# B134X.net
KiCad netlist of a schematic drawn in EAGLE
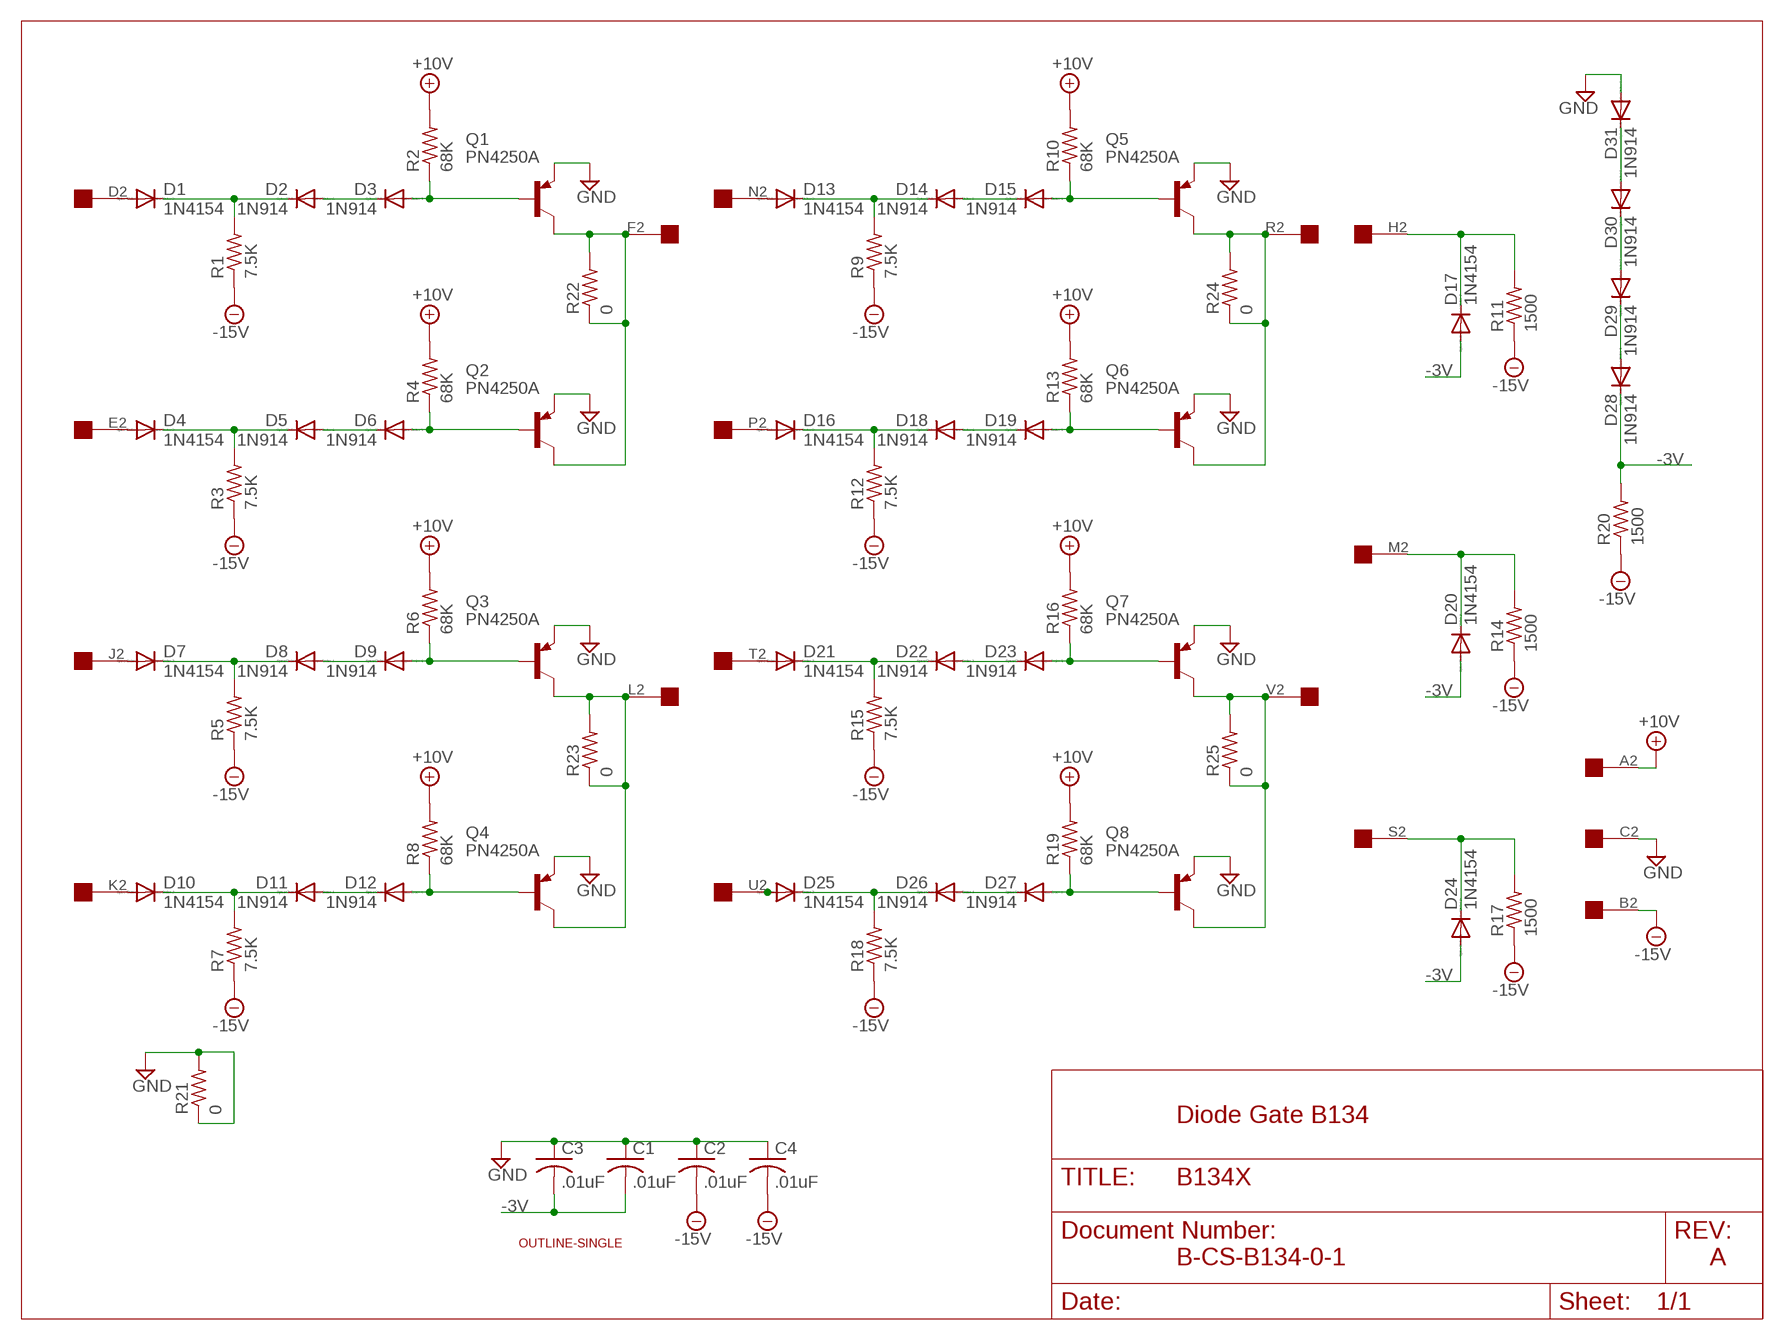
[diagram p0: schematic, sheet 1]

(export (version "E")
  (design (tool "Eeschema 10.0.6"))
  (components
    (comp (ref "C1")
      (value ".01uF")
      (footprint "eagle-import:C063-025X075")
      (libsource (lib "eagle-import") (part "C-US"))
    )
    (comp (ref "C2")
      (value ".01uF")
      (footprint "eagle-import:C063-025X075")
      (libsource (lib "eagle-import") (part "C-US"))
    )
    (comp (ref "C3")
      (value ".01uF")
      (footprint "eagle-import:C063-025X075")
      (libsource (lib "eagle-import") (part "C-US"))
    )
    (comp (ref "C4")
      (value ".01uF")
      (footprint "eagle-import:C063-025X075")
      (libsource (lib "eagle-import") (part "C-US"))
    )
    (comp (ref "D1")
      (value "1N4154")
      (footprint "eagle-import:DO35-10")
      (libsource (lib "eagle-import") (part "DIODE-DO35-10"))
    )
    (comp (ref "D2")
      (value "1N914")
      (footprint "eagle-import:DO35-10")
      (libsource (lib "eagle-import") (part "DIODE-DO35-10"))
    )
    (comp (ref "D3")
      (value "1N914")
      (footprint "eagle-import:DO35-10")
      (libsource (lib "eagle-import") (part "DIODE-DO35-10"))
    )
    (comp (ref "D4")
      (value "1N4154")
      (footprint "eagle-import:DO35-10")
      (libsource (lib "eagle-import") (part "DIODE-DO35-10"))
    )
    (comp (ref "D5")
      (value "1N914")
      (footprint "eagle-import:DO35-10")
      (libsource (lib "eagle-import") (part "DIODE-DO35-10"))
    )
    (comp (ref "D6")
      (value "1N914")
      (footprint "eagle-import:DO35-10")
      (libsource (lib "eagle-import") (part "DIODE-DO35-10"))
    )
    (comp (ref "D7")
      (value "1N4154")
      (footprint "eagle-import:DO35-10")
      (libsource (lib "eagle-import") (part "DIODE-DO35-10"))
    )
    (comp (ref "D8")
      (value "1N914")
      (footprint "eagle-import:DO35-10")
      (libsource (lib "eagle-import") (part "DIODE-DO35-10"))
    )
    (comp (ref "D9")
      (value "1N914")
      (footprint "eagle-import:DO35-10")
      (libsource (lib "eagle-import") (part "DIODE-DO35-10"))
    )
    (comp (ref "D10")
      (value "1N4154")
      (footprint "eagle-import:DO35-10")
      (libsource (lib "eagle-import") (part "DIODE-DO35-10"))
    )
    (comp (ref "D11")
      (value "1N914")
      (footprint "eagle-import:DO35-10")
      (libsource (lib "eagle-import") (part "DIODE-DO35-10"))
    )
    (comp (ref "D12")
      (value "1N914")
      (footprint "eagle-import:DO35-10")
      (libsource (lib "eagle-import") (part "DIODE-DO35-10"))
    )
    (comp (ref "D13")
      (value "1N4154")
      (footprint "eagle-import:DO35-10")
      (libsource (lib "eagle-import") (part "DIODE-DO35-10"))
    )
    (comp (ref "D14")
      (value "1N914")
      (footprint "eagle-import:DO35-10")
      (libsource (lib "eagle-import") (part "DIODE-DO35-10"))
    )
    (comp (ref "D15")
      (value "1N914")
      (footprint "eagle-import:DO35-10")
      (libsource (lib "eagle-import") (part "DIODE-DO35-10"))
    )
    (comp (ref "D16")
      (value "1N4154")
      (footprint "eagle-import:DO35-10")
      (libsource (lib "eagle-import") (part "DIODE-DO35-10"))
    )
    (comp (ref "D17")
      (value "1N4154")
      (footprint "eagle-import:DO35-10")
      (libsource (lib "eagle-import") (part "DIODE-DO35-10"))
    )
    (comp (ref "D18")
      (value "1N914")
      (footprint "eagle-import:DO35-10")
      (libsource (lib "eagle-import") (part "DIODE-DO35-10"))
    )
    (comp (ref "D19")
      (value "1N914")
      (footprint "eagle-import:DO35-10")
      (libsource (lib "eagle-import") (part "DIODE-DO35-10"))
    )
    (comp (ref "D20")
      (value "1N4154")
      (footprint "eagle-import:DO35-10")
      (libsource (lib "eagle-import") (part "DIODE-DO35-10"))
    )
    (comp (ref "D21")
      (value "1N4154")
      (footprint "eagle-import:DO35-10")
      (libsource (lib "eagle-import") (part "DIODE-DO35-10"))
    )
    (comp (ref "D22")
      (value "1N914")
      (footprint "eagle-import:DO35-10")
      (libsource (lib "eagle-import") (part "DIODE-DO35-10"))
    )
    (comp (ref "D23")
      (value "1N914")
      (footprint "eagle-import:DO35-10")
      (libsource (lib "eagle-import") (part "DIODE-DO35-10"))
    )
    (comp (ref "D24")
      (value "1N4154")
      (footprint "eagle-import:DO35-10")
      (libsource (lib "eagle-import") (part "DIODE-DO35-10"))
    )
    (comp (ref "D25")
      (value "1N4154")
      (footprint "eagle-import:DO35-10")
      (libsource (lib "eagle-import") (part "DIODE-DO35-10"))
    )
    (comp (ref "D26")
      (value "1N914")
      (footprint "eagle-import:DO35-10")
      (libsource (lib "eagle-import") (part "DIODE-DO35-10"))
    )
    (comp (ref "D27")
      (value "1N914")
      (footprint "eagle-import:DO35-10")
      (libsource (lib "eagle-import") (part "DIODE-DO35-10"))
    )
    (comp (ref "D28")
      (value "1N914")
      (footprint "eagle-import:DO35-10")
      (libsource (lib "eagle-import") (part "DIODE-DO35-10"))
    )
    (comp (ref "D29")
      (value "1N914")
      (footprint "eagle-import:DO35-10")
      (libsource (lib "eagle-import") (part "DIODE-DO35-10"))
    )
    (comp (ref "D30")
      (value "1N914")
      (footprint "eagle-import:DO35-10")
      (libsource (lib "eagle-import") (part "DIODE-DO35-10"))
    )
    (comp (ref "D31")
      (value "1N914")
      (footprint "eagle-import:DO35-10")
      (libsource (lib "eagle-import") (part "DIODE-DO35-10"))
    )
    (comp (ref "Q1")
      (value "PN4250A")
      (footprint "eagle-import:TO5")
      (libsource (lib "eagle-import") (part "-PNP-TO5"))
    )
    (comp (ref "Q2")
      (value "PN4250A")
      (footprint "eagle-import:TO5")
      (libsource (lib "eagle-import") (part "-PNP-TO5"))
    )
    (comp (ref "Q3")
      (value "PN4250A")
      (footprint "eagle-import:TO5")
      (libsource (lib "eagle-import") (part "-PNP-TO5"))
    )
    (comp (ref "Q4")
      (value "PN4250A")
      (footprint "eagle-import:TO5")
      (libsource (lib "eagle-import") (part "-PNP-TO5"))
    )
    (comp (ref "Q5")
      (value "PN4250A")
      (footprint "eagle-import:TO5")
      (libsource (lib "eagle-import") (part "-PNP-TO5"))
    )
    (comp (ref "Q6")
      (value "PN4250A")
      (footprint "eagle-import:TO5")
      (libsource (lib "eagle-import") (part "-PNP-TO5"))
    )
    (comp (ref "Q7")
      (value "PN4250A")
      (footprint "eagle-import:TO5")
      (libsource (lib "eagle-import") (part "-PNP-TO5"))
    )
    (comp (ref "Q8")
      (value "PN4250A")
      (footprint "eagle-import:TO5")
      (libsource (lib "eagle-import") (part "-PNP-TO5"))
    )
    (comp (ref "R1")
      (value "7.5K")
      (footprint "eagle-import:0207_10")
      (libsource (lib "eagle-import") (part "R-US_0207/10"))
    )
    (comp (ref "R2")
      (value "68K")
      (footprint "eagle-import:0207_10")
      (libsource (lib "eagle-import") (part "R-US_0207/10"))
    )
    (comp (ref "R3")
      (value "7.5K")
      (footprint "eagle-import:0207_10")
      (libsource (lib "eagle-import") (part "R-US_0207/10"))
    )
    (comp (ref "R4")
      (value "68K")
      (footprint "eagle-import:0207_10")
      (libsource (lib "eagle-import") (part "R-US_0207/10"))
    )
    (comp (ref "R5")
      (value "7.5K")
      (footprint "eagle-import:0207_10")
      (libsource (lib "eagle-import") (part "R-US_0207/10"))
    )
    (comp (ref "R6")
      (value "68K")
      (footprint "eagle-import:0207_10")
      (libsource (lib "eagle-import") (part "R-US_0207/10"))
    )
    (comp (ref "R7")
      (value "7.5K")
      (footprint "eagle-import:0207_10")
      (libsource (lib "eagle-import") (part "R-US_0207/10"))
    )
    (comp (ref "R8")
      (value "68K")
      (footprint "eagle-import:0207_10")
      (libsource (lib "eagle-import") (part "R-US_0207/10"))
    )
    (comp (ref "R9")
      (value "7.5K")
      (footprint "eagle-import:0207_10")
      (libsource (lib "eagle-import") (part "R-US_0207/10"))
    )
    (comp (ref "R10")
      (value "68K")
      (footprint "eagle-import:0207_10")
      (libsource (lib "eagle-import") (part "R-US_0207/10"))
    )
    (comp (ref "R11")
      (value "1500")
      (footprint "eagle-import:0207_10")
      (libsource (lib "eagle-import") (part "R-US_0207/10"))
    )
    (comp (ref "R12")
      (value "7.5K")
      (footprint "eagle-import:0207_10")
      (libsource (lib "eagle-import") (part "R-US_0207/10"))
    )
    (comp (ref "R13")
      (value "68K")
      (footprint "eagle-import:0207_10")
      (libsource (lib "eagle-import") (part "R-US_0207/10"))
    )
    (comp (ref "R14")
      (value "1500")
      (footprint "eagle-import:0207_10")
      (libsource (lib "eagle-import") (part "R-US_0207/10"))
    )
    (comp (ref "R15")
      (value "7.5K")
      (footprint "eagle-import:0207_10")
      (libsource (lib "eagle-import") (part "R-US_0207/10"))
    )
    (comp (ref "R16")
      (value "68K")
      (footprint "eagle-import:0207_10")
      (libsource (lib "eagle-import") (part "R-US_0207/10"))
    )
    (comp (ref "R17")
      (value "1500")
      (footprint "eagle-import:0207_10")
      (libsource (lib "eagle-import") (part "R-US_0207/10"))
    )
    (comp (ref "R18")
      (value "7.5K")
      (footprint "eagle-import:0207_10")
      (libsource (lib "eagle-import") (part "R-US_0207/10"))
    )
    (comp (ref "R19")
      (value "68K")
      (footprint "eagle-import:0207_10")
      (libsource (lib "eagle-import") (part "R-US_0207/10"))
    )
    (comp (ref "R20")
      (value "1500")
      (footprint "eagle-import:0207_10")
      (libsource (lib "eagle-import") (part "R-US_0207/10"))
    )
    (comp (ref "R21")
      (value "0")
      (footprint "eagle-import:0207_10")
      (libsource (lib "eagle-import") (part "R-US_0207/10"))
    )
    (comp (ref "R22")
      (value "0")
      (footprint "eagle-import:0207_10")
      (libsource (lib "eagle-import") (part "R-US_0207/10"))
    )
    (comp (ref "R23")
      (value "0")
      (footprint "eagle-import:0207_10")
      (libsource (lib "eagle-import") (part "R-US_0207/10"))
    )
    (comp (ref "R24")
      (value "0")
      (footprint "eagle-import:0207_10")
      (libsource (lib "eagle-import") (part "R-US_0207/10"))
    )
    (comp (ref "R25")
      (value "0")
      (footprint "eagle-import:0207_10")
      (libsource (lib "eagle-import") (part "R-US_0207/10"))
    )
    (comp (ref "U$1")
      (value "OUTLINE-SINGLE")
      (footprint "eagle-import:SINGLE")
      (libsource (lib "eagle-import") (part "OUTLINE-SINGLE"))
    )
    (comp (ref "U$2")
      (value "EDGE-1")
      (footprint "eagle-import:EDGE-CON1")
      (libsource (lib "eagle-import") (part "EDGE-1"))
    )
  )
  (nets
    (net (code "1") (name "+10V") (class "Default")
      (node (ref "R10") (pin "2") (pinfunction "2_2") (pintype "passive"))
      (node (ref "R13") (pin "2") (pinfunction "2_2") (pintype "passive"))
      (node (ref "R16") (pin "2") (pinfunction "2_2") (pintype "passive"))
      (node (ref "R19") (pin "2") (pinfunction "2_2") (pintype "passive"))
      (node (ref "R2") (pin "2") (pinfunction "2_2") (pintype "passive"))
      (node (ref "R4") (pin "2") (pinfunction "2_2") (pintype "passive"))
      (node (ref "R6") (pin "2") (pinfunction "2_2") (pintype "passive"))
      (node (ref "R8") (pin "2") (pinfunction "2_2") (pintype "passive"))
      (node (ref "U$2") (pin "A2") (pinfunction "1_A2") (pintype "bidirectional"))
    )
    (net (code "2") (name "-15V") (class "Default")
      (node (ref "C2") (pin "2") (pinfunction "2_2") (pintype "passive"))
      (node (ref "C4") (pin "2") (pinfunction "2_2") (pintype "passive"))
      (node (ref "R1") (pin "1") (pinfunction "1_1") (pintype "passive"))
      (node (ref "R11") (pin "1") (pinfunction "1_1") (pintype "passive"))
      (node (ref "R12") (pin "1") (pinfunction "1_1") (pintype "passive"))
      (node (ref "R14") (pin "1") (pinfunction "1_1") (pintype "passive"))
      (node (ref "R15") (pin "1") (pinfunction "1_1") (pintype "passive"))
      (node (ref "R17") (pin "1") (pinfunction "1_1") (pintype "passive"))
      (node (ref "R18") (pin "1") (pinfunction "1_1") (pintype "passive"))
      (node (ref "R20") (pin "1") (pinfunction "1_1") (pintype "passive"))
      (node (ref "R3") (pin "1") (pinfunction "1_1") (pintype "passive"))
      (node (ref "R5") (pin "1") (pinfunction "1_1") (pintype "passive"))
      (node (ref "R7") (pin "1") (pinfunction "1_1") (pintype "passive"))
      (node (ref "R9") (pin "1") (pinfunction "1_1") (pintype "passive"))
      (node (ref "U$2") (pin "B2") (pinfunction "1_B2") (pintype "bidirectional"))
    )
    (net (code "3") (name "/-3V") (class "Default")
      (node (ref "C1") (pin "2") (pinfunction "2_2") (pintype "passive"))
      (node (ref "C3") (pin "2") (pinfunction "2_2") (pintype "passive"))
      (node (ref "D17") (pin "A") (pinfunction "A_A") (pintype "passive"))
      (node (ref "D20") (pin "A") (pinfunction "A_A") (pintype "passive"))
      (node (ref "D24") (pin "A") (pinfunction "A_A") (pintype "passive"))
      (node (ref "D28") (pin "C") (pinfunction "C_C") (pintype "passive"))
      (node (ref "R20") (pin "2") (pinfunction "2_2") (pintype "passive"))
    )
    (net (code "4") (name "GND") (class "Default")
      (node (ref "C1") (pin "1") (pinfunction "1_1") (pintype "passive"))
      (node (ref "C2") (pin "1") (pinfunction "1_1") (pintype "passive"))
      (node (ref "C3") (pin "1") (pinfunction "1_1") (pintype "passive"))
      (node (ref "C4") (pin "1") (pinfunction "1_1") (pintype "passive"))
      (node (ref "D31") (pin "A") (pinfunction "A_A") (pintype "passive"))
      (node (ref "Q1") (pin "1") (pinfunction "E_1") (pintype "passive"))
      (node (ref "Q2") (pin "1") (pinfunction "E_1") (pintype "passive"))
      (node (ref "Q3") (pin "1") (pinfunction "E_1") (pintype "passive"))
      (node (ref "Q4") (pin "1") (pinfunction "E_1") (pintype "passive"))
      (node (ref "Q5") (pin "1") (pinfunction "E_1") (pintype "passive"))
      (node (ref "Q6") (pin "1") (pinfunction "E_1") (pintype "passive"))
      (node (ref "Q7") (pin "1") (pinfunction "E_1") (pintype "passive"))
      (node (ref "Q8") (pin "1") (pinfunction "E_1") (pintype "passive"))
      (node (ref "R21") (pin "1") (pinfunction "1_1") (pintype "passive"))
      (node (ref "R21") (pin "2") (pinfunction "2_2") (pintype "passive"))
      (node (ref "U$2") (pin "C2") (pinfunction "1_C2") (pintype "bidirectional"))
    )
    (net (code "5") (name "Net-(D1-PadC)") (class "Default")
      (node (ref "D1") (pin "C") (pinfunction "C_C") (pintype "passive"))
      (node (ref "D2") (pin "C") (pinfunction "C_C") (pintype "passive"))
      (node (ref "R1") (pin "2") (pinfunction "2_2") (pintype "passive"))
    )
    (net (code "6") (name "Net-(D2-PadA)") (class "Default")
      (node (ref "D2") (pin "A") (pinfunction "A_A") (pintype "passive"))
      (node (ref "D3") (pin "C") (pinfunction "C_C") (pintype "passive"))
    )
    (net (code "7") (name "Net-(D4-PadC)") (class "Default")
      (node (ref "D4") (pin "C") (pinfunction "C_C") (pintype "passive"))
      (node (ref "D5") (pin "C") (pinfunction "C_C") (pintype "passive"))
      (node (ref "R3") (pin "2") (pinfunction "2_2") (pintype "passive"))
    )
    (net (code "8") (name "Net-(D5-PadA)") (class "Default")
      (node (ref "D5") (pin "A") (pinfunction "A_A") (pintype "passive"))
      (node (ref "D6") (pin "C") (pinfunction "C_C") (pintype "passive"))
    )
    (net (code "9") (name "Net-(D7-PadC)") (class "Default")
      (node (ref "D7") (pin "C") (pinfunction "C_C") (pintype "passive"))
      (node (ref "D8") (pin "C") (pinfunction "C_C") (pintype "passive"))
      (node (ref "R5") (pin "2") (pinfunction "2_2") (pintype "passive"))
    )
    (net (code "10") (name "Net-(D8-PadA)") (class "Default")
      (node (ref "D8") (pin "A") (pinfunction "A_A") (pintype "passive"))
      (node (ref "D9") (pin "C") (pinfunction "C_C") (pintype "passive"))
    )
    (net (code "11") (name "Net-(D10-PadC)") (class "Default")
      (node (ref "D10") (pin "C") (pinfunction "C_C") (pintype "passive"))
      (node (ref "D11") (pin "C") (pinfunction "C_C") (pintype "passive"))
      (node (ref "R7") (pin "2") (pinfunction "2_2") (pintype "passive"))
    )
    (net (code "12") (name "Net-(D11-PadA)") (class "Default")
      (node (ref "D11") (pin "A") (pinfunction "A_A") (pintype "passive"))
      (node (ref "D12") (pin "C") (pinfunction "C_C") (pintype "passive"))
    )
    (net (code "13") (name "Net-(D13-PadC)") (class "Default")
      (node (ref "D13") (pin "C") (pinfunction "C_C") (pintype "passive"))
      (node (ref "D14") (pin "C") (pinfunction "C_C") (pintype "passive"))
      (node (ref "R9") (pin "2") (pinfunction "2_2") (pintype "passive"))
    )
    (net (code "14") (name "Net-(D14-PadA)") (class "Default")
      (node (ref "D14") (pin "A") (pinfunction "A_A") (pintype "passive"))
      (node (ref "D15") (pin "C") (pinfunction "C_C") (pintype "passive"))
    )
    (net (code "15") (name "Net-(D16-PadC)") (class "Default")
      (node (ref "D16") (pin "C") (pinfunction "C_C") (pintype "passive"))
      (node (ref "D18") (pin "C") (pinfunction "C_C") (pintype "passive"))
      (node (ref "R12") (pin "2") (pinfunction "2_2") (pintype "passive"))
    )
    (net (code "16") (name "Net-(D18-PadA)") (class "Default")
      (node (ref "D18") (pin "A") (pinfunction "A_A") (pintype "passive"))
      (node (ref "D19") (pin "C") (pinfunction "C_C") (pintype "passive"))
    )
    (net (code "17") (name "Net-(D21-PadC)") (class "Default")
      (node (ref "D21") (pin "C") (pinfunction "C_C") (pintype "passive"))
      (node (ref "D22") (pin "C") (pinfunction "C_C") (pintype "passive"))
      (node (ref "R15") (pin "2") (pinfunction "2_2") (pintype "passive"))
    )
    (net (code "18") (name "Net-(D22-PadA)") (class "Default")
      (node (ref "D22") (pin "A") (pinfunction "A_A") (pintype "passive"))
      (node (ref "D23") (pin "C") (pinfunction "C_C") (pintype "passive"))
    )
    (net (code "19") (name "Net-(D25-PadC)") (class "Default")
      (node (ref "D25") (pin "C") (pinfunction "C_C") (pintype "passive"))
      (node (ref "D26") (pin "C") (pinfunction "C_C") (pintype "passive"))
      (node (ref "R18") (pin "2") (pinfunction "2_2") (pintype "passive"))
    )
    (net (code "20") (name "Net-(D26-PadA)") (class "Default")
      (node (ref "D26") (pin "A") (pinfunction "A_A") (pintype "passive"))
      (node (ref "D27") (pin "C") (pinfunction "C_C") (pintype "passive"))
    )
    (net (code "21") (name "Net-(D28-PadA)") (class "Default")
      (node (ref "D28") (pin "A") (pinfunction "A_A") (pintype "passive"))
      (node (ref "D29") (pin "C") (pinfunction "C_C") (pintype "passive"))
    )
    (net (code "22") (name "Net-(D29-PadA)") (class "Default")
      (node (ref "D29") (pin "A") (pinfunction "A_A") (pintype "passive"))
      (node (ref "D30") (pin "C") (pinfunction "C_C") (pintype "passive"))
    )
    (net (code "23") (name "Net-(D30-PadA)") (class "Default")
      (node (ref "D30") (pin "A") (pinfunction "A_A") (pintype "passive"))
      (node (ref "D31") (pin "C") (pinfunction "C_C") (pintype "passive"))
    )
    (net (code "24") (name "Net-(Q1-B)") (class "Default")
      (node (ref "D3") (pin "A") (pinfunction "A_A") (pintype "passive"))
      (node (ref "Q1") (pin "2") (pinfunction "B_2") (pintype "passive"))
      (node (ref "R2") (pin "1") (pinfunction "1_1") (pintype "passive"))
    )
    (net (code "25") (name "Net-(Q1-C)") (class "Default")
      (node (ref "Q1") (pin "3") (pinfunction "C_3") (pintype "passive"))
      (node (ref "Q2") (pin "3") (pinfunction "C_3") (pintype "passive"))
      (node (ref "R22") (pin "1") (pinfunction "1_1") (pintype "passive"))
      (node (ref "R22") (pin "2") (pinfunction "2_2") (pintype "passive"))
      (node (ref "U$2") (pin "F2") (pinfunction "1_F2") (pintype "bidirectional"))
    )
    (net (code "26") (name "Net-(Q2-B)") (class "Default")
      (node (ref "D6") (pin "A") (pinfunction "A_A") (pintype "passive"))
      (node (ref "Q2") (pin "2") (pinfunction "B_2") (pintype "passive"))
      (node (ref "R4") (pin "1") (pinfunction "1_1") (pintype "passive"))
    )
    (net (code "27") (name "Net-(Q3-B)") (class "Default")
      (node (ref "D9") (pin "A") (pinfunction "A_A") (pintype "passive"))
      (node (ref "Q3") (pin "2") (pinfunction "B_2") (pintype "passive"))
      (node (ref "R6") (pin "1") (pinfunction "1_1") (pintype "passive"))
    )
    (net (code "28") (name "Net-(Q3-C)") (class "Default")
      (node (ref "Q3") (pin "3") (pinfunction "C_3") (pintype "passive"))
      (node (ref "Q4") (pin "3") (pinfunction "C_3") (pintype "passive"))
      (node (ref "R23") (pin "1") (pinfunction "1_1") (pintype "passive"))
      (node (ref "R23") (pin "2") (pinfunction "2_2") (pintype "passive"))
      (node (ref "U$2") (pin "L2") (pinfunction "1_L2") (pintype "bidirectional"))
    )
    (net (code "29") (name "Net-(Q4-B)") (class "Default")
      (node (ref "D12") (pin "A") (pinfunction "A_A") (pintype "passive"))
      (node (ref "Q4") (pin "2") (pinfunction "B_2") (pintype "passive"))
      (node (ref "R8") (pin "1") (pinfunction "1_1") (pintype "passive"))
    )
    (net (code "30") (name "Net-(Q5-B)") (class "Default")
      (node (ref "D15") (pin "A") (pinfunction "A_A") (pintype "passive"))
      (node (ref "Q5") (pin "2") (pinfunction "B_2") (pintype "passive"))
      (node (ref "R10") (pin "1") (pinfunction "1_1") (pintype "passive"))
    )
    (net (code "31") (name "Net-(Q5-C)") (class "Default")
      (node (ref "Q5") (pin "3") (pinfunction "C_3") (pintype "passive"))
      (node (ref "Q6") (pin "3") (pinfunction "C_3") (pintype "passive"))
      (node (ref "R24") (pin "1") (pinfunction "1_1") (pintype "passive"))
      (node (ref "R24") (pin "2") (pinfunction "2_2") (pintype "passive"))
      (node (ref "U$2") (pin "R2") (pinfunction "1_R2") (pintype "bidirectional"))
    )
    (net (code "32") (name "Net-(Q6-B)") (class "Default")
      (node (ref "D19") (pin "A") (pinfunction "A_A") (pintype "passive"))
      (node (ref "Q6") (pin "2") (pinfunction "B_2") (pintype "passive"))
      (node (ref "R13") (pin "1") (pinfunction "1_1") (pintype "passive"))
    )
    (net (code "33") (name "Net-(Q7-B)") (class "Default")
      (node (ref "D23") (pin "A") (pinfunction "A_A") (pintype "passive"))
      (node (ref "Q7") (pin "2") (pinfunction "B_2") (pintype "passive"))
      (node (ref "R16") (pin "1") (pinfunction "1_1") (pintype "passive"))
    )
    (net (code "34") (name "Net-(Q7-C)") (class "Default")
      (node (ref "Q7") (pin "3") (pinfunction "C_3") (pintype "passive"))
      (node (ref "Q8") (pin "3") (pinfunction "C_3") (pintype "passive"))
      (node (ref "R25") (pin "1") (pinfunction "1_1") (pintype "passive"))
      (node (ref "R25") (pin "2") (pinfunction "2_2") (pintype "passive"))
      (node (ref "U$2") (pin "V2") (pinfunction "1_V2") (pintype "bidirectional"))
    )
    (net (code "35") (name "Net-(Q8-B)") (class "Default")
      (node (ref "D27") (pin "A") (pinfunction "A_A") (pintype "passive"))
      (node (ref "Q8") (pin "2") (pinfunction "B_2") (pintype "passive"))
      (node (ref "R19") (pin "1") (pinfunction "1_1") (pintype "passive"))
    )
    (net (code "36") (name "Net-(U$2D-1)") (class "Default")
      (node (ref "D1") (pin "A") (pinfunction "A_A") (pintype "passive"))
      (node (ref "U$2") (pin "D2") (pinfunction "1_D2") (pintype "bidirectional"))
    )
    (net (code "37") (name "Net-(U$2E-1)") (class "Default")
      (node (ref "D4") (pin "A") (pinfunction "A_A") (pintype "passive"))
      (node (ref "U$2") (pin "E2") (pinfunction "1_E2") (pintype "bidirectional"))
    )
    (net (code "38") (name "Net-(U$2G-1)") (class "Default")
      (node (ref "D17") (pin "C") (pinfunction "C_C") (pintype "passive"))
      (node (ref "R11") (pin "2") (pinfunction "2_2") (pintype "passive"))
      (node (ref "U$2") (pin "H2") (pinfunction "1_H2") (pintype "bidirectional"))
    )
    (net (code "39") (name "Net-(U$2H-1)") (class "Default")
      (node (ref "D7") (pin "A") (pinfunction "A_A") (pintype "passive"))
      (node (ref "U$2") (pin "J2") (pinfunction "1_J2") (pintype "bidirectional"))
    )
    (net (code "40") (name "Net-(U$2I-1)") (class "Default")
      (node (ref "D10") (pin "A") (pinfunction "A_A") (pintype "passive"))
      (node (ref "U$2") (pin "K2") (pinfunction "1_K2") (pintype "bidirectional"))
    )
    (net (code "41") (name "Net-(U$2K-1)") (class "Default")
      (node (ref "D20") (pin "C") (pinfunction "C_C") (pintype "passive"))
      (node (ref "R14") (pin "2") (pinfunction "2_2") (pintype "passive"))
      (node (ref "U$2") (pin "M2") (pinfunction "1_M2") (pintype "bidirectional"))
    )
    (net (code "42") (name "Net-(U$2L-1)") (class "Default")
      (node (ref "D13") (pin "A") (pinfunction "A_A") (pintype "passive"))
      (node (ref "U$2") (pin "N2") (pinfunction "1_N2") (pintype "bidirectional"))
    )
    (net (code "43") (name "Net-(U$2M-1)") (class "Default")
      (node (ref "D16") (pin "A") (pinfunction "A_A") (pintype "passive"))
      (node (ref "U$2") (pin "P2") (pinfunction "1_P2") (pintype "bidirectional"))
    )
    (net (code "44") (name "Net-(U$2O-1)") (class "Default")
      (node (ref "D24") (pin "C") (pinfunction "C_C") (pintype "passive"))
      (node (ref "R17") (pin "2") (pinfunction "2_2") (pintype "passive"))
      (node (ref "U$2") (pin "S2") (pinfunction "1_S2") (pintype "bidirectional"))
    )
    (net (code "45") (name "Net-(U$2P-1)") (class "Default")
      (node (ref "D21") (pin "A") (pinfunction "A_A") (pintype "passive"))
      (node (ref "U$2") (pin "T2") (pinfunction "1_T2") (pintype "bidirectional"))
    )
    (net (code "46") (name "Net-(U$2Q-1)") (class "Default")
      (node (ref "D25") (pin "A") (pinfunction "A_A") (pintype "passive"))
      (node (ref "U$2") (pin "U2") (pinfunction "1_U2") (pintype "bidirectional"))
    )
  )
)
